# LED_Module.net
KiCad netlist of a schematic drawn in Altium Designer
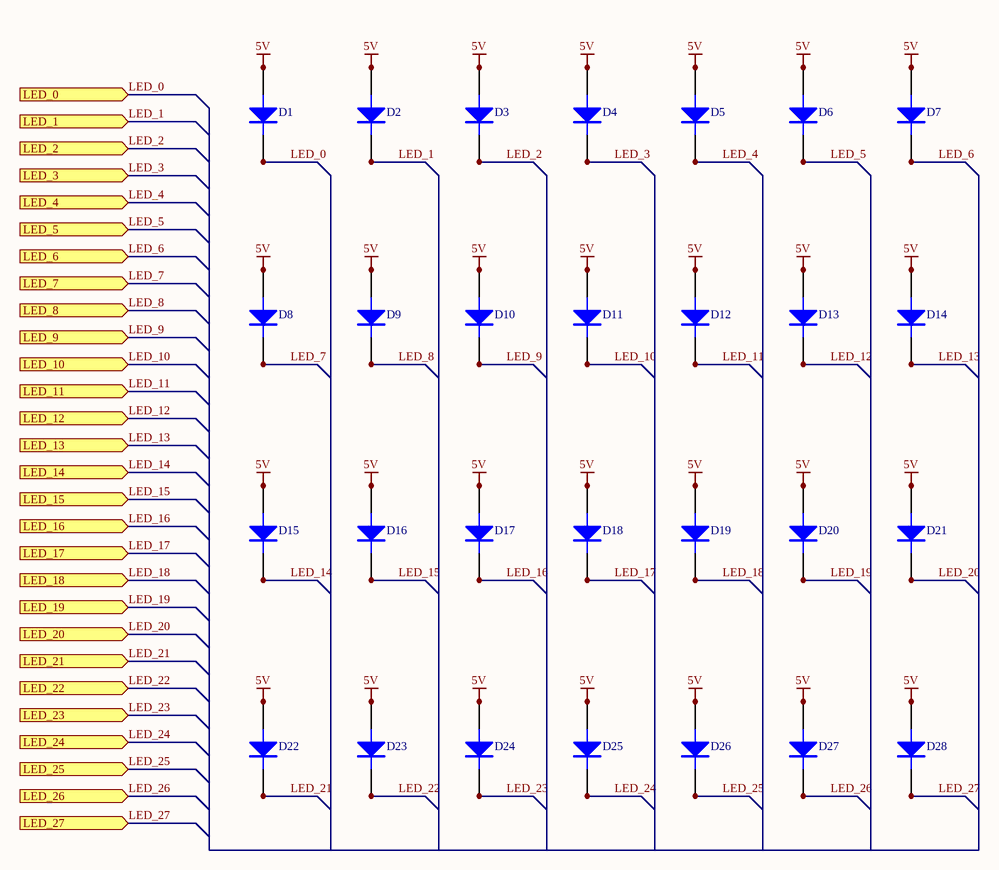
[diagram p0: LED Module.SchDoc]

(export (version "E")
  (design (tool "Eeschema 10.0.6"))
  (components
    (comp (ref "D1")
      (value "AMBER")
      (footprint "CREE P4 YELLOW")
      (description "CREE AMBER LED P4 (SUPERFLUX)")
      (libsource (lib "LED TAIL LIGHTS") (part "CP41B-AFSCM0Q0264"))
    )
    (comp (ref "D2")
      (value "AMBER")
      (footprint "CREE P4 YELLOW")
      (description "CREE AMBER LED P4 (SUPERFLUX)")
      (libsource (lib "LED TAIL LIGHTS") (part "CP41B-AFSCM0Q0264"))
    )
    (comp (ref "D3")
      (value "AMBER")
      (footprint "CREE P4 YELLOW")
      (description "CREE AMBER LED P4 (SUPERFLUX)")
      (libsource (lib "LED TAIL LIGHTS") (part "CP41B-AFSCM0Q0264"))
    )
    (comp (ref "D4")
      (value "AMBER")
      (footprint "CREE P4 YELLOW")
      (description "CREE AMBER LED P4 (SUPERFLUX)")
      (libsource (lib "LED TAIL LIGHTS") (part "CP41B-AFSCM0Q0264"))
    )
    (comp (ref "D5")
      (value "AMBER")
      (footprint "CREE P4 YELLOW")
      (description "CREE AMBER LED P4 (SUPERFLUX)")
      (libsource (lib "LED TAIL LIGHTS") (part "CP41B-AFSCM0Q0264"))
    )
    (comp (ref "D6")
      (value "AMBER")
      (footprint "CREE P4 YELLOW")
      (description "CREE AMBER LED P4 (SUPERFLUX)")
      (libsource (lib "LED TAIL LIGHTS") (part "CP41B-AFSCM0Q0264"))
    )
    (comp (ref "D7")
      (value "AMBER")
      (footprint "CREE P4 YELLOW")
      (description "CREE AMBER LED P4 (SUPERFLUX)")
      (libsource (lib "LED TAIL LIGHTS") (part "CP41B-AFSCM0Q0264"))
    )
    (comp (ref "D8")
      (value "AMBER")
      (footprint "CREE P4 YELLOW")
      (description "CREE AMBER LED P4 (SUPERFLUX)")
      (libsource (lib "LED TAIL LIGHTS") (part "CP41B-AFSCM0Q0264"))
    )
    (comp (ref "D9")
      (value "AMBER")
      (footprint "CREE P4 YELLOW")
      (description "CREE AMBER LED P4 (SUPERFLUX)")
      (libsource (lib "LED TAIL LIGHTS") (part "CP41B-AFSCM0Q0264"))
    )
    (comp (ref "D10")
      (value "AMBER")
      (footprint "CREE P4 YELLOW")
      (description "CREE AMBER LED P4 (SUPERFLUX)")
      (libsource (lib "LED TAIL LIGHTS") (part "CP41B-AFSCM0Q0264"))
    )
    (comp (ref "D11")
      (value "AMBER")
      (footprint "CREE P4 YELLOW")
      (description "CREE AMBER LED P4 (SUPERFLUX)")
      (libsource (lib "LED TAIL LIGHTS") (part "CP41B-AFSCM0Q0264"))
    )
    (comp (ref "D12")
      (value "AMBER")
      (footprint "CREE P4 YELLOW")
      (description "CREE AMBER LED P4 (SUPERFLUX)")
      (libsource (lib "LED TAIL LIGHTS") (part "CP41B-AFSCM0Q0264"))
    )
    (comp (ref "D13")
      (value "AMBER")
      (footprint "CREE P4 YELLOW")
      (description "CREE AMBER LED P4 (SUPERFLUX)")
      (libsource (lib "LED TAIL LIGHTS") (part "CP41B-AFSCM0Q0264"))
    )
    (comp (ref "D14")
      (value "AMBER")
      (footprint "CREE P4 YELLOW")
      (description "CREE AMBER LED P4 (SUPERFLUX)")
      (libsource (lib "LED TAIL LIGHTS") (part "CP41B-AFSCM0Q0264"))
    )
    (comp (ref "D15")
      (value "AMBER")
      (footprint "CREE P4 YELLOW")
      (description "CREE AMBER LED P4 (SUPERFLUX)")
      (libsource (lib "LED TAIL LIGHTS") (part "CP41B-AFSCM0Q0264"))
    )
    (comp (ref "D16")
      (value "AMBER")
      (footprint "CREE P4 YELLOW")
      (description "CREE AMBER LED P4 (SUPERFLUX)")
      (libsource (lib "LED TAIL LIGHTS") (part "CP41B-AFSCM0Q0264"))
    )
    (comp (ref "D17")
      (value "AMBER")
      (footprint "CREE P4 YELLOW")
      (description "CREE AMBER LED P4 (SUPERFLUX)")
      (libsource (lib "LED TAIL LIGHTS") (part "CP41B-AFSCM0Q0264"))
    )
    (comp (ref "D18")
      (value "AMBER")
      (footprint "CREE P4 YELLOW")
      (description "CREE AMBER LED P4 (SUPERFLUX)")
      (libsource (lib "LED TAIL LIGHTS") (part "CP41B-AFSCM0Q0264"))
    )
    (comp (ref "D19")
      (value "AMBER")
      (footprint "CREE P4 YELLOW")
      (description "CREE AMBER LED P4 (SUPERFLUX)")
      (libsource (lib "LED TAIL LIGHTS") (part "CP41B-AFSCM0Q0264"))
    )
    (comp (ref "D20")
      (value "AMBER")
      (footprint "CREE P4 YELLOW")
      (description "CREE AMBER LED P4 (SUPERFLUX)")
      (libsource (lib "LED TAIL LIGHTS") (part "CP41B-AFSCM0Q0264"))
    )
    (comp (ref "D21")
      (value "AMBER")
      (footprint "CREE P4 YELLOW")
      (description "CREE AMBER LED P4 (SUPERFLUX)")
      (libsource (lib "LED TAIL LIGHTS") (part "CP41B-AFSCM0Q0264"))
    )
    (comp (ref "D22")
      (value "AMBER")
      (footprint "CREE P4 YELLOW")
      (description "CREE AMBER LED P4 (SUPERFLUX)")
      (libsource (lib "LED TAIL LIGHTS") (part "CP41B-AFSCM0Q0264"))
    )
    (comp (ref "D23")
      (value "AMBER")
      (footprint "CREE P4 YELLOW")
      (description "CREE AMBER LED P4 (SUPERFLUX)")
      (libsource (lib "LED TAIL LIGHTS") (part "CP41B-AFSCM0Q0264"))
    )
    (comp (ref "D24")
      (value "AMBER")
      (footprint "CREE P4 YELLOW")
      (description "CREE AMBER LED P4 (SUPERFLUX)")
      (libsource (lib "LED TAIL LIGHTS") (part "CP41B-AFSCM0Q0264"))
    )
    (comp (ref "D25")
      (value "AMBER")
      (footprint "CREE P4 YELLOW")
      (description "CREE AMBER LED P4 (SUPERFLUX)")
      (libsource (lib "LED TAIL LIGHTS") (part "CP41B-AFSCM0Q0264"))
    )
    (comp (ref "D26")
      (value "AMBER")
      (footprint "CREE P4 YELLOW")
      (description "CREE AMBER LED P4 (SUPERFLUX)")
      (libsource (lib "LED TAIL LIGHTS") (part "CP41B-AFSCM0Q0264"))
    )
    (comp (ref "D27")
      (value "AMBER")
      (footprint "CREE P4 YELLOW")
      (description "CREE AMBER LED P4 (SUPERFLUX)")
      (libsource (lib "LED TAIL LIGHTS") (part "CP41B-AFSCM0Q0264"))
    )
    (comp (ref "D28")
      (value "AMBER")
      (footprint "CREE P4 YELLOW")
      (description "CREE AMBER LED P4 (SUPERFLUX)")
      (libsource (lib "LED TAIL LIGHTS") (part "CP41B-AFSCM0Q0264"))
    )
  )
  (nets
    (net (code "1") (name "/LED_0") (class "Default")
      (node (ref "D1") (pin "1") (pinfunction "K_1") (pintype "passive"))
      (node (ref "D1") (pin "4") (pinfunction "K_4") (pintype "passive"))
    )
    (net (code "2") (name "/LED_1") (class "Default")
      (node (ref "D2") (pin "1") (pinfunction "K_1") (pintype "passive"))
      (node (ref "D2") (pin "4") (pinfunction "K_4") (pintype "passive"))
    )
    (net (code "3") (name "/LED_2") (class "Default")
      (node (ref "D3") (pin "1") (pinfunction "K_1") (pintype "passive"))
      (node (ref "D3") (pin "4") (pinfunction "K_4") (pintype "passive"))
    )
    (net (code "4") (name "/LED_3") (class "Default")
      (node (ref "D4") (pin "1") (pinfunction "K_1") (pintype "passive"))
      (node (ref "D4") (pin "4") (pinfunction "K_4") (pintype "passive"))
    )
    (net (code "5") (name "/LED_4") (class "Default")
      (node (ref "D5") (pin "1") (pinfunction "K_1") (pintype "passive"))
      (node (ref "D5") (pin "4") (pinfunction "K_4") (pintype "passive"))
    )
    (net (code "6") (name "/LED_5") (class "Default")
      (node (ref "D6") (pin "1") (pinfunction "K_1") (pintype "passive"))
      (node (ref "D6") (pin "4") (pinfunction "K_4") (pintype "passive"))
    )
    (net (code "7") (name "/LED_6") (class "Default")
      (node (ref "D7") (pin "1") (pinfunction "K_1") (pintype "passive"))
      (node (ref "D7") (pin "4") (pinfunction "K_4") (pintype "passive"))
    )
    (net (code "8") (name "/LED_7") (class "Default")
      (node (ref "D8") (pin "1") (pinfunction "K_1") (pintype "passive"))
      (node (ref "D8") (pin "4") (pinfunction "K_4") (pintype "passive"))
    )
    (net (code "9") (name "/LED_8") (class "Default")
      (node (ref "D9") (pin "1") (pinfunction "K_1") (pintype "passive"))
      (node (ref "D9") (pin "4") (pinfunction "K_4") (pintype "passive"))
    )
    (net (code "10") (name "/LED_9") (class "Default")
      (node (ref "D10") (pin "1") (pinfunction "K_1") (pintype "passive"))
      (node (ref "D10") (pin "4") (pinfunction "K_4") (pintype "passive"))
    )
    (net (code "11") (name "/LED_10") (class "Default")
      (node (ref "D11") (pin "1") (pinfunction "K_1") (pintype "passive"))
      (node (ref "D11") (pin "4") (pinfunction "K_4") (pintype "passive"))
    )
    (net (code "12") (name "/LED_11") (class "Default")
      (node (ref "D12") (pin "1") (pinfunction "K_1") (pintype "passive"))
      (node (ref "D12") (pin "4") (pinfunction "K_4") (pintype "passive"))
    )
    (net (code "13") (name "/LED_12") (class "Default")
      (node (ref "D13") (pin "1") (pinfunction "K_1") (pintype "passive"))
      (node (ref "D13") (pin "4") (pinfunction "K_4") (pintype "passive"))
    )
    (net (code "14") (name "/LED_13") (class "Default")
      (node (ref "D14") (pin "1") (pinfunction "K_1") (pintype "passive"))
      (node (ref "D14") (pin "4") (pinfunction "K_4") (pintype "passive"))
    )
    (net (code "15") (name "/LED_14") (class "Default")
      (node (ref "D15") (pin "1") (pinfunction "K_1") (pintype "passive"))
      (node (ref "D15") (pin "4") (pinfunction "K_4") (pintype "passive"))
    )
    (net (code "16") (name "/LED_15") (class "Default")
      (node (ref "D16") (pin "1") (pinfunction "K_1") (pintype "passive"))
      (node (ref "D16") (pin "4") (pinfunction "K_4") (pintype "passive"))
    )
    (net (code "17") (name "/LED_16") (class "Default")
      (node (ref "D17") (pin "1") (pinfunction "K_1") (pintype "passive"))
      (node (ref "D17") (pin "4") (pinfunction "K_4") (pintype "passive"))
    )
    (net (code "18") (name "/LED_17") (class "Default")
      (node (ref "D18") (pin "1") (pinfunction "K_1") (pintype "passive"))
      (node (ref "D18") (pin "4") (pinfunction "K_4") (pintype "passive"))
    )
    (net (code "19") (name "/LED_18") (class "Default")
      (node (ref "D19") (pin "1") (pinfunction "K_1") (pintype "passive"))
      (node (ref "D19") (pin "4") (pinfunction "K_4") (pintype "passive"))
    )
    (net (code "20") (name "/LED_19") (class "Default")
      (node (ref "D20") (pin "1") (pinfunction "K_1") (pintype "passive"))
      (node (ref "D20") (pin "4") (pinfunction "K_4") (pintype "passive"))
    )
    (net (code "21") (name "/LED_20") (class "Default")
      (node (ref "D21") (pin "1") (pinfunction "K_1") (pintype "passive"))
      (node (ref "D21") (pin "4") (pinfunction "K_4") (pintype "passive"))
    )
    (net (code "22") (name "/LED_21") (class "Default")
      (node (ref "D22") (pin "1") (pinfunction "K_1") (pintype "passive"))
      (node (ref "D22") (pin "4") (pinfunction "K_4") (pintype "passive"))
    )
    (net (code "23") (name "/LED_22") (class "Default")
      (node (ref "D23") (pin "1") (pinfunction "K_1") (pintype "passive"))
      (node (ref "D23") (pin "4") (pinfunction "K_4") (pintype "passive"))
    )
    (net (code "24") (name "/LED_23") (class "Default")
      (node (ref "D24") (pin "1") (pinfunction "K_1") (pintype "passive"))
      (node (ref "D24") (pin "4") (pinfunction "K_4") (pintype "passive"))
    )
    (net (code "25") (name "/LED_24") (class "Default")
      (node (ref "D25") (pin "1") (pinfunction "K_1") (pintype "passive"))
      (node (ref "D25") (pin "4") (pinfunction "K_4") (pintype "passive"))
    )
    (net (code "26") (name "/LED_25") (class "Default")
      (node (ref "D26") (pin "1") (pinfunction "K_1") (pintype "passive"))
      (node (ref "D26") (pin "4") (pinfunction "K_4") (pintype "passive"))
    )
    (net (code "27") (name "/LED_26") (class "Default")
      (node (ref "D27") (pin "1") (pinfunction "K_1") (pintype "passive"))
      (node (ref "D27") (pin "4") (pinfunction "K_4") (pintype "passive"))
    )
    (net (code "28") (name "/LED_27") (class "Default")
      (node (ref "D28") (pin "1") (pinfunction "K_1") (pintype "passive"))
      (node (ref "D28") (pin "4") (pinfunction "K_4") (pintype "passive"))
    )
    (net (code "29") (name "5V") (class "Default")
      (node (ref "D1") (pin "2") (pinfunction "A_2") (pintype "passive"))
      (node (ref "D1") (pin "3") (pinfunction "A_3") (pintype "passive"))
      (node (ref "D10") (pin "2") (pinfunction "A_2") (pintype "passive"))
      (node (ref "D10") (pin "3") (pinfunction "A_3") (pintype "passive"))
      (node (ref "D11") (pin "2") (pinfunction "A_2") (pintype "passive"))
      (node (ref "D11") (pin "3") (pinfunction "A_3") (pintype "passive"))
      (node (ref "D12") (pin "2") (pinfunction "A_2") (pintype "passive"))
      (node (ref "D12") (pin "3") (pinfunction "A_3") (pintype "passive"))
      (node (ref "D13") (pin "2") (pinfunction "A_2") (pintype "passive"))
      (node (ref "D13") (pin "3") (pinfunction "A_3") (pintype "passive"))
      (node (ref "D14") (pin "2") (pinfunction "A_2") (pintype "passive"))
      (node (ref "D14") (pin "3") (pinfunction "A_3") (pintype "passive"))
      (node (ref "D15") (pin "2") (pinfunction "A_2") (pintype "passive"))
      (node (ref "D15") (pin "3") (pinfunction "A_3") (pintype "passive"))
      (node (ref "D16") (pin "2") (pinfunction "A_2") (pintype "passive"))
      (node (ref "D16") (pin "3") (pinfunction "A_3") (pintype "passive"))
      (node (ref "D17") (pin "2") (pinfunction "A_2") (pintype "passive"))
      (node (ref "D17") (pin "3") (pinfunction "A_3") (pintype "passive"))
      (node (ref "D18") (pin "2") (pinfunction "A_2") (pintype "passive"))
      (node (ref "D18") (pin "3") (pinfunction "A_3") (pintype "passive"))
      (node (ref "D19") (pin "2") (pinfunction "A_2") (pintype "passive"))
      (node (ref "D19") (pin "3") (pinfunction "A_3") (pintype "passive"))
      (node (ref "D2") (pin "2") (pinfunction "A_2") (pintype "passive"))
      (node (ref "D2") (pin "3") (pinfunction "A_3") (pintype "passive"))
      (node (ref "D20") (pin "2") (pinfunction "A_2") (pintype "passive"))
      (node (ref "D20") (pin "3") (pinfunction "A_3") (pintype "passive"))
      (node (ref "D21") (pin "2") (pinfunction "A_2") (pintype "passive"))
      (node (ref "D21") (pin "3") (pinfunction "A_3") (pintype "passive"))
      (node (ref "D22") (pin "2") (pinfunction "A_2") (pintype "passive"))
      (node (ref "D22") (pin "3") (pinfunction "A_3") (pintype "passive"))
      (node (ref "D23") (pin "2") (pinfunction "A_2") (pintype "passive"))
      (node (ref "D23") (pin "3") (pinfunction "A_3") (pintype "passive"))
      (node (ref "D24") (pin "2") (pinfunction "A_2") (pintype "passive"))
      (node (ref "D24") (pin "3") (pinfunction "A_3") (pintype "passive"))
      (node (ref "D25") (pin "2") (pinfunction "A_2") (pintype "passive"))
      (node (ref "D25") (pin "3") (pinfunction "A_3") (pintype "passive"))
      (node (ref "D26") (pin "2") (pinfunction "A_2") (pintype "passive"))
      (node (ref "D26") (pin "3") (pinfunction "A_3") (pintype "passive"))
      (node (ref "D27") (pin "2") (pinfunction "A_2") (pintype "passive"))
      (node (ref "D27") (pin "3") (pinfunction "A_3") (pintype "passive"))
      (node (ref "D28") (pin "2") (pinfunction "A_2") (pintype "passive"))
      (node (ref "D28") (pin "3") (pinfunction "A_3") (pintype "passive"))
      (node (ref "D3") (pin "2") (pinfunction "A_2") (pintype "passive"))
      (node (ref "D3") (pin "3") (pinfunction "A_3") (pintype "passive"))
      (node (ref "D4") (pin "2") (pinfunction "A_2") (pintype "passive"))
      (node (ref "D4") (pin "3") (pinfunction "A_3") (pintype "passive"))
      (node (ref "D5") (pin "2") (pinfunction "A_2") (pintype "passive"))
      (node (ref "D5") (pin "3") (pinfunction "A_3") (pintype "passive"))
      (node (ref "D6") (pin "2") (pinfunction "A_2") (pintype "passive"))
      (node (ref "D6") (pin "3") (pinfunction "A_3") (pintype "passive"))
      (node (ref "D7") (pin "2") (pinfunction "A_2") (pintype "passive"))
      (node (ref "D7") (pin "3") (pinfunction "A_3") (pintype "passive"))
      (node (ref "D8") (pin "2") (pinfunction "A_2") (pintype "passive"))
      (node (ref "D8") (pin "3") (pinfunction "A_3") (pintype "passive"))
      (node (ref "D9") (pin "2") (pinfunction "A_2") (pintype "passive"))
      (node (ref "D9") (pin "3") (pinfunction "A_3") (pintype "passive"))
    )
  )
)
